# D1MPOWER.net
KiCad netlist of a schematic drawn in EAGLE
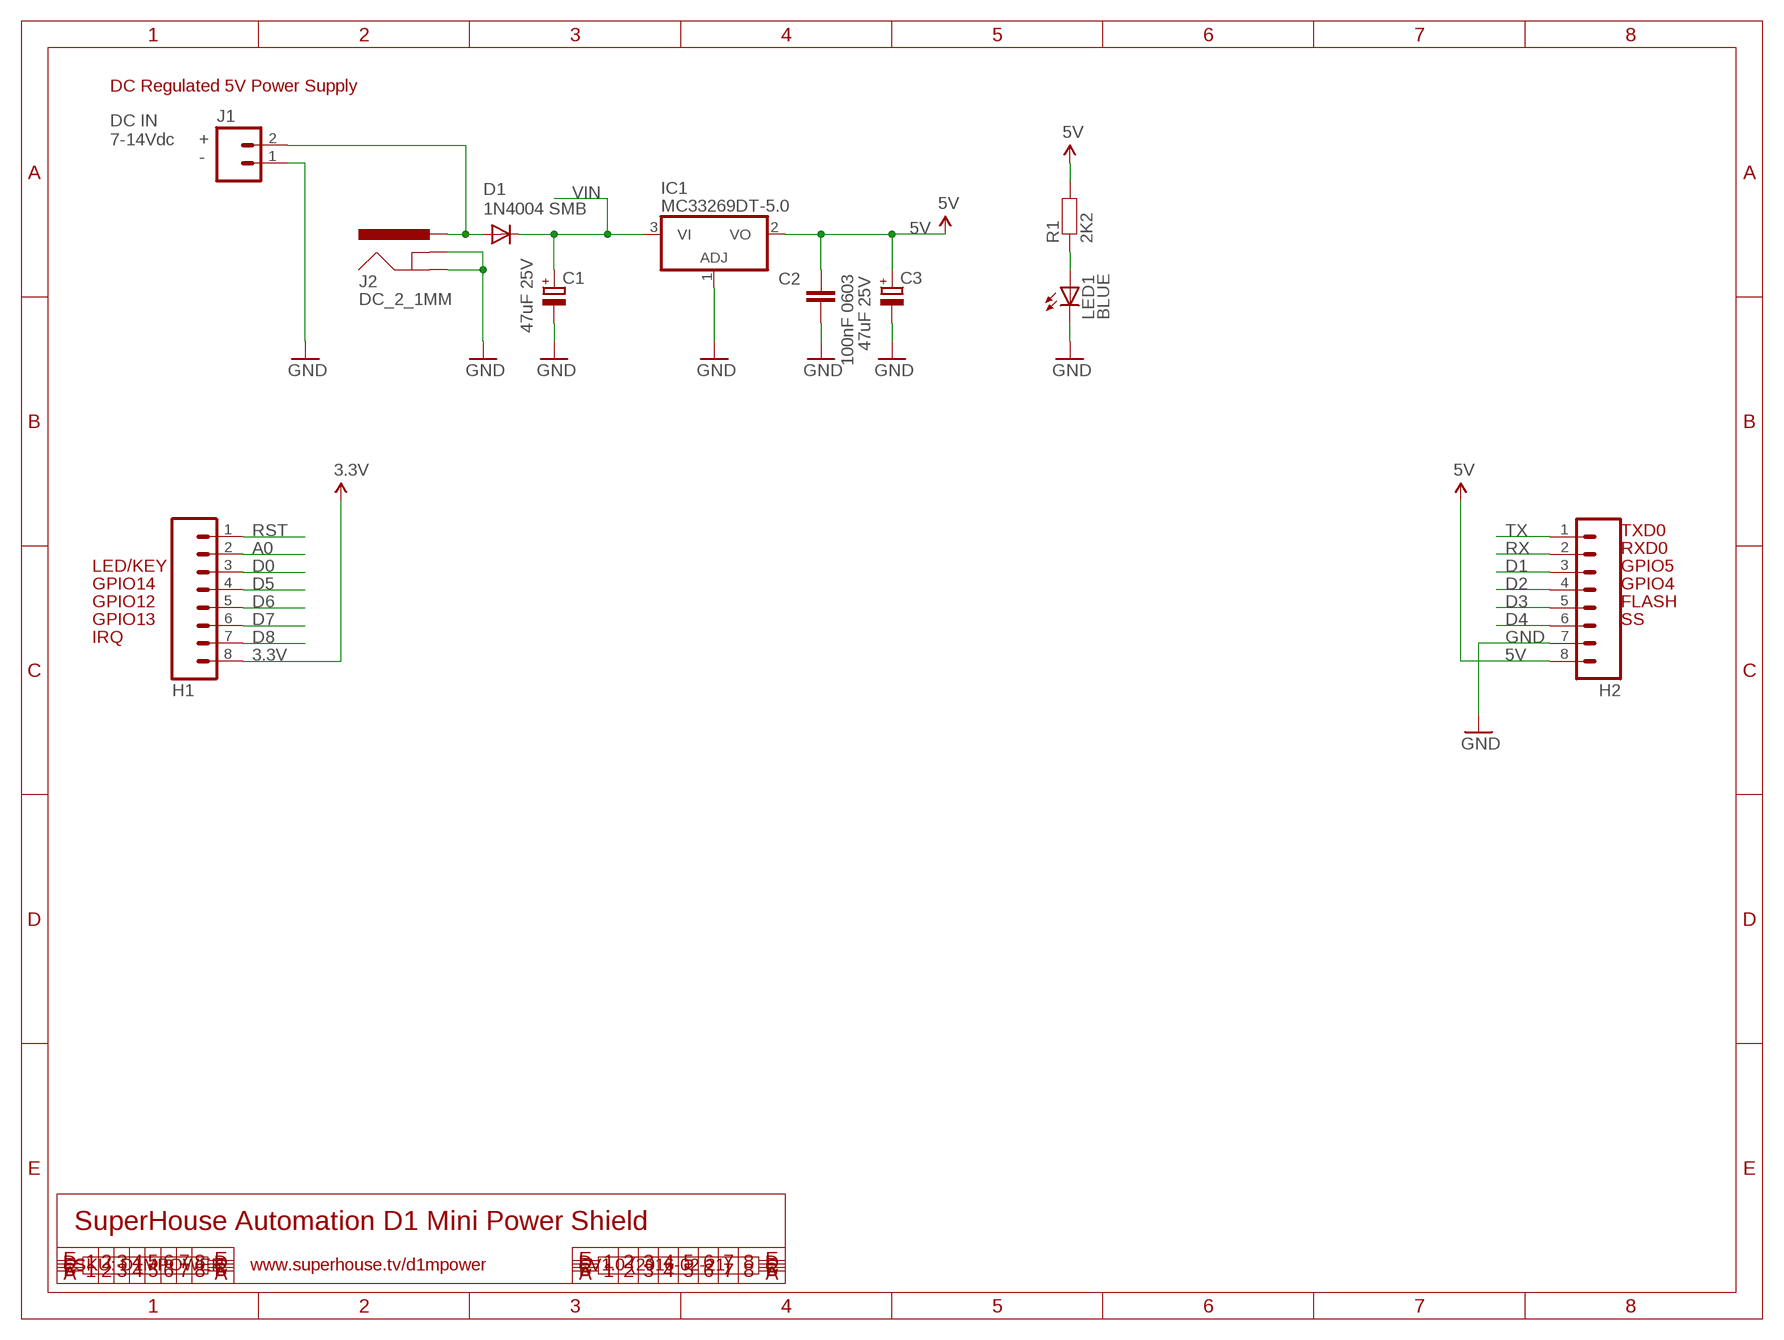
[diagram p0: schematic, sheet 1]

(export (version "E")
  (design (tool "Eeschema 10.0.6"))
  (components
    (comp (ref "C1")
      (value "47uF 25V")
      (footprint "eagle-import:PANASONIC_D")
      (libsource (lib "eagle-import") (part "CPOL-EUD"))
    )
    (comp (ref "C2")
      (value "100nF 0603")
      (footprint "eagle-import:0603")
      (libsource (lib "eagle-import") (part "CAP0603"))
    )
    (comp (ref "C3")
      (value "47uF 25V")
      (footprint "eagle-import:PANASONIC_D")
      (libsource (lib "eagle-import") (part "CPOL-EUD"))
    )
    (comp (ref "D1")
      (value "1N4004 SMB")
      (footprint "eagle-import:SMB-DIODE")
      (libsource (lib "eagle-import") (part "DIODESMB"))
    )
    (comp (ref "H1")
      (value "M08")
      (footprint "eagle-import:1X08")
      (libsource (lib "eagle-import") (part "M08"))
    )
    (comp (ref "H2")
      (value "M08")
      (footprint "eagle-import:1X08")
      (libsource (lib "eagle-import") (part "M08"))
    )
    (comp (ref "IC1")
      (value "MC33269DT-5.0")
      (footprint "eagle-import:DPACK")
      (libsource (lib "eagle-import") (part "MC33269?D-5.0"))
    )
    (comp (ref "J1")
      (value "M023.5MM")
      (footprint "eagle-import:SCREWTERMINAL-3.5MM-2")
      (libsource (lib "eagle-import") (part "M023.5MM"))
    )
    (comp (ref "J2")
      (value "DC_2_1MM")
      (footprint "eagle-import:POWER_JACK_PTH")
      (libsource (lib "eagle-import") (part "POWER_JACKPTH"))
    )
    (comp (ref "LED1")
      (value "BLUE")
      (footprint "eagle-import:LED-0603")
      (libsource (lib "eagle-import") (part "LED0603"))
    )
    (comp (ref "R1")
      (value "2K2")
      (footprint "eagle-import:0603")
      (libsource (lib "eagle-import") (part "RESISTOR0603"))
    )
  )
  (nets
    (net (code "1") (name "/A0") (class "Default")
      (node (ref "H1") (pin "2") (pinfunction "2_2") (pintype "passive"))
    )
    (net (code "2") (name "/D0") (class "Default")
      (node (ref "H1") (pin "3") (pinfunction "3_3") (pintype "passive"))
    )
    (net (code "3") (name "/D1") (class "Default")
      (node (ref "H2") (pin "3") (pinfunction "3_3") (pintype "passive"))
    )
    (net (code "4") (name "/D2") (class "Default")
      (node (ref "H2") (pin "4") (pinfunction "4_4") (pintype "passive"))
    )
    (net (code "5") (name "/D3") (class "Default")
      (node (ref "H2") (pin "5") (pinfunction "5_5") (pintype "passive"))
    )
    (net (code "6") (name "/D4") (class "Default")
      (node (ref "H2") (pin "6") (pinfunction "6_6") (pintype "passive"))
    )
    (net (code "7") (name "/D5") (class "Default")
      (node (ref "H1") (pin "4") (pinfunction "4_4") (pintype "passive"))
    )
    (net (code "8") (name "/D6") (class "Default")
      (node (ref "H1") (pin "5") (pinfunction "5_5") (pintype "passive"))
    )
    (net (code "9") (name "/D7") (class "Default")
      (node (ref "H1") (pin "6") (pinfunction "6_6") (pintype "passive"))
    )
    (net (code "10") (name "/D8") (class "Default")
      (node (ref "H1") (pin "7") (pinfunction "7_7") (pintype "passive"))
    )
    (net (code "11") (name "/RST") (class "Default")
      (node (ref "H1") (pin "1") (pinfunction "1_1") (pintype "passive"))
    )
    (net (code "12") (name "/RX") (class "Default")
      (node (ref "H2") (pin "2") (pinfunction "2_2") (pintype "passive"))
    )
    (net (code "13") (name "/TX") (class "Default")
      (node (ref "H2") (pin "1") (pinfunction "1_1") (pintype "passive"))
    )
    (net (code "14") (name "/VIN") (class "Default")
      (node (ref "C1") (pin "+") (pinfunction "+_+") (pintype "passive"))
      (node (ref "D1") (pin "C") (pinfunction "C_C") (pintype "passive"))
      (node (ref "IC1") (pin "3") (pinfunction "VI_3") (pintype "input"))
    )
    (net (code "15") (name "3.3V") (class "Default")
      (node (ref "H1") (pin "8") (pinfunction "8_8") (pintype "passive"))
    )
    (net (code "16") (name "5V") (class "Default")
      (node (ref "C2") (pin "1") (pinfunction "1_1") (pintype "passive"))
      (node (ref "C3") (pin "+") (pinfunction "+_+") (pintype "passive"))
      (node (ref "H2") (pin "8") (pinfunction "8_8") (pintype "passive"))
      (node (ref "IC1") (pin "2") (pinfunction "VO_2") (pintype "passive"))
      (node (ref "R1") (pin "2") (pinfunction "2_2") (pintype "passive"))
    )
    (net (code "17") (name "GND") (class "Default")
      (node (ref "C1") (pin "-") (pinfunction "-_-") (pintype "passive"))
      (node (ref "C2") (pin "2") (pinfunction "2_2") (pintype "passive"))
      (node (ref "C3") (pin "-") (pinfunction "-_-") (pintype "passive"))
      (node (ref "H2") (pin "7") (pinfunction "7_7") (pintype "passive"))
      (node (ref "IC1") (pin "1") (pinfunction "ADJ_1") (pintype "input"))
      (node (ref "J1") (pin "1") (pinfunction "1_1") (pintype "passive"))
      (node (ref "J2") (pin "GND") (pinfunction "GND_GND") (pintype "bidirectional"))
      (node (ref "J2") (pin "GNDBREAK") (pinfunction "GNDBREAK_GNDBREAK") (pintype "bidirectional"))
      (node (ref "LED1") (pin "C") (pinfunction "C_C") (pintype "passive"))
    )
    (net (code "18") (name "Net-(D1-PadA)") (class "Default")
      (node (ref "D1") (pin "A") (pinfunction "A_A") (pintype "passive"))
      (node (ref "J1") (pin "2") (pinfunction "2_2") (pintype "passive"))
      (node (ref "J2") (pin "PWR") (pinfunction "PWR_PWR") (pintype "bidirectional"))
    )
    (net (code "19") (name "Net-(LED1-PadA)") (class "Default")
      (node (ref "LED1") (pin "A") (pinfunction "A_A") (pintype "passive"))
      (node (ref "R1") (pin "1") (pinfunction "1_1") (pintype "passive"))
    )
  )
)
